# RF_Block.net
KiCad netlist of a schematic drawn in Altium Designer
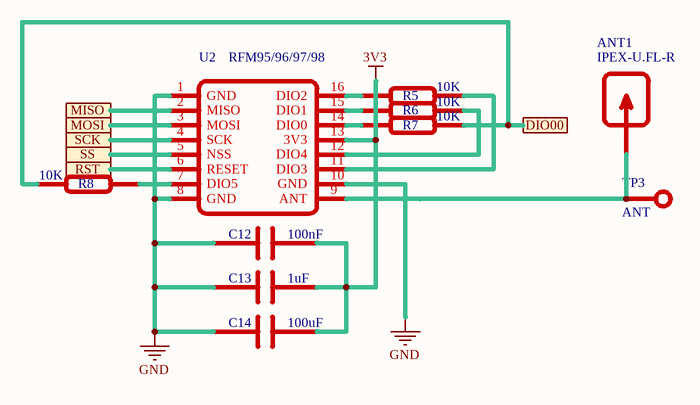
[diagram p0: RF_Block.SchDoc]

(export (version "E")
  (design (tool "Eeschema 10.0.6"))
  (components
    (comp (ref "ANT1")
      (value "IPEX-U.FL-R")
      (footprint "IPEX Connector SMD")
      (description "RF Antena")
      (libsource (lib "CTAI-Library") (part "IPEX-U.FL-R"))
    )
    (comp (ref "C12")
      (value "100nF")
      (footprint "C0805")
      (description "Ceramic Capacitor")
      (libsource (lib "CTAI-Library") (part "CAP-CER"))
    )
    (comp (ref "C13")
      (value "1uF")
      (footprint "C0805")
      (description "Ceramic Capacitor")
      (libsource (lib "CTAI-Library") (part "CAP-CER"))
    )
    (comp (ref "C14")
      (value "100uF")
      (footprint "C0805")
      (description "Ceramic Capacitor")
      (libsource (lib "CTAI-Library") (part "CAP-CER"))
    )
    (comp (ref "R5")
      (value "10K")
      (footprint "R0805")
      (description "Resistor")
      (libsource (lib "CTAI-Library") (part "Resistor"))
    )
    (comp (ref "R6")
      (value "10K")
      (footprint "R0805")
      (description "Resistor")
      (libsource (lib "CTAI-Library") (part "Resistor"))
    )
    (comp (ref "R7")
      (value "10K")
      (footprint "R0603")
      (description "Resistor")
      (libsource (lib "CTAI-Library") (part "Resistor"))
    )
    (comp (ref "R8")
      (value "10K")
      (footprint "R0603")
      (description "Resistor")
      (libsource (lib "CTAI-Library") (part "Resistor"))
    )
    (comp (ref "TP3")
      (value "ANT")
      (footprint "Test Point")
      (description "Test Point")
      (libsource (lib "CTAI-Library") (part "TestPoint"))
    )
    (comp (ref "U2")
      (value "RFM95/96/97/98")
      (footprint "LORA RFM95/96/97/98W")
      (libsource (lib "CTAI-Library") (part "RFM95/96/97/98 LORA Module"))
    )
  )
  (nets
    (net (code "1") (name "/DIO00") (class "Default")
      (node (ref "R7") (pin "2") (pinfunction "2_2") (pintype "passive"))
      (node (ref "R8") (pin "1") (pinfunction "1_1") (pintype "passive"))
    )
    (net (code "2") (name "/MISO") (class "Default")
      (node (ref "U2") (pin "2") (pinfunction "MISO_2") (pintype "passive"))
    )
    (net (code "3") (name "/MOSI") (class "Default")
      (node (ref "U2") (pin "3") (pinfunction "MOSI_3") (pintype "passive"))
    )
    (net (code "4") (name "/RST") (class "Default")
      (node (ref "U2") (pin "6") (pinfunction "RESET_6") (pintype "passive"))
    )
    (net (code "5") (name "/SCK") (class "Default")
      (node (ref "U2") (pin "4") (pinfunction "SCK_4") (pintype "passive"))
    )
    (net (code "6") (name "/SS") (class "Default")
      (node (ref "U2") (pin "5") (pinfunction "NSS_5") (pintype "passive"))
    )
    (net (code "7") (name "3V3") (class "Default")
      (node (ref "C12") (pin "2") (pintype "passive"))
      (node (ref "C13") (pin "2") (pintype "passive"))
      (node (ref "C14") (pin "2") (pintype "passive"))
      (node (ref "U2") (pin "13") (pinfunction "3V3_13") (pintype "passive"))
    )
    (net (code "8") (name "GND") (class "Default")
      (node (ref "C12") (pin "1") (pintype "passive"))
      (node (ref "C13") (pin "1") (pintype "passive"))
      (node (ref "C14") (pin "1") (pintype "passive"))
      (node (ref "U2") (pin "1") (pinfunction "GND_1") (pintype "passive"))
      (node (ref "U2") (pin "10") (pinfunction "GND_10") (pintype "passive"))
      (node (ref "U2") (pin "8") (pinfunction "GND_8") (pintype "passive"))
    )
    (net (code "9") (name "Net-(U2-ANT)") (class "Default")
      (node (ref "ANT1") (pin "1") (pinfunction "1_1") (pintype "passive"))
      (node (ref "TP3") (pin "1") (pinfunction "1_1") (pintype "passive"))
      (node (ref "U2") (pin "9") (pinfunction "ANT_9") (pintype "passive"))
    )
    (net (code "10") (name "Net-(U2-DIO0)") (class "Default")
      (node (ref "R7") (pin "1") (pinfunction "1_1") (pintype "passive"))
      (node (ref "U2") (pin "14") (pinfunction "DIO0_14") (pintype "passive"))
    )
    (net (code "11") (name "Net-(U2-DIO1)") (class "Default")
      (node (ref "R6") (pin "1") (pinfunction "1_1") (pintype "passive"))
      (node (ref "U2") (pin "15") (pinfunction "DIO1_15") (pintype "passive"))
    )
    (net (code "12") (name "Net-(U2-DIO2)") (class "Default")
      (node (ref "R5") (pin "1") (pinfunction "1_1") (pintype "passive"))
      (node (ref "U2") (pin "16") (pinfunction "DIO2_16") (pintype "passive"))
    )
    (net (code "13") (name "Net-(U2-DIO3)") (class "Default")
      (node (ref "R5") (pin "2") (pinfunction "2_2") (pintype "passive"))
      (node (ref "U2") (pin "11") (pinfunction "DIO3_11") (pintype "passive"))
    )
    (net (code "14") (name "Net-(U2-DIO4)") (class "Default")
      (node (ref "R6") (pin "2") (pinfunction "2_2") (pintype "passive"))
      (node (ref "U2") (pin "12") (pinfunction "DIO4_12") (pintype "passive"))
    )
    (net (code "15") (name "Net-(U2-DIO5)") (class "Default")
      (node (ref "R8") (pin "2") (pinfunction "2_2") (pintype "passive"))
      (node (ref "U2") (pin "7") (pinfunction "DIO5_7") (pintype "passive"))
    )
    (net (code "16") (name "unconnected-(ANT1-GND-Pad2)") (class "Default")
      (node (ref "ANT1") (pin "2") (pinfunction "GND_2") (pintype "passive"))
    )
  )
)
